# USB_MUX.net
KiCad netlist of a schematic drawn in Altium Designer
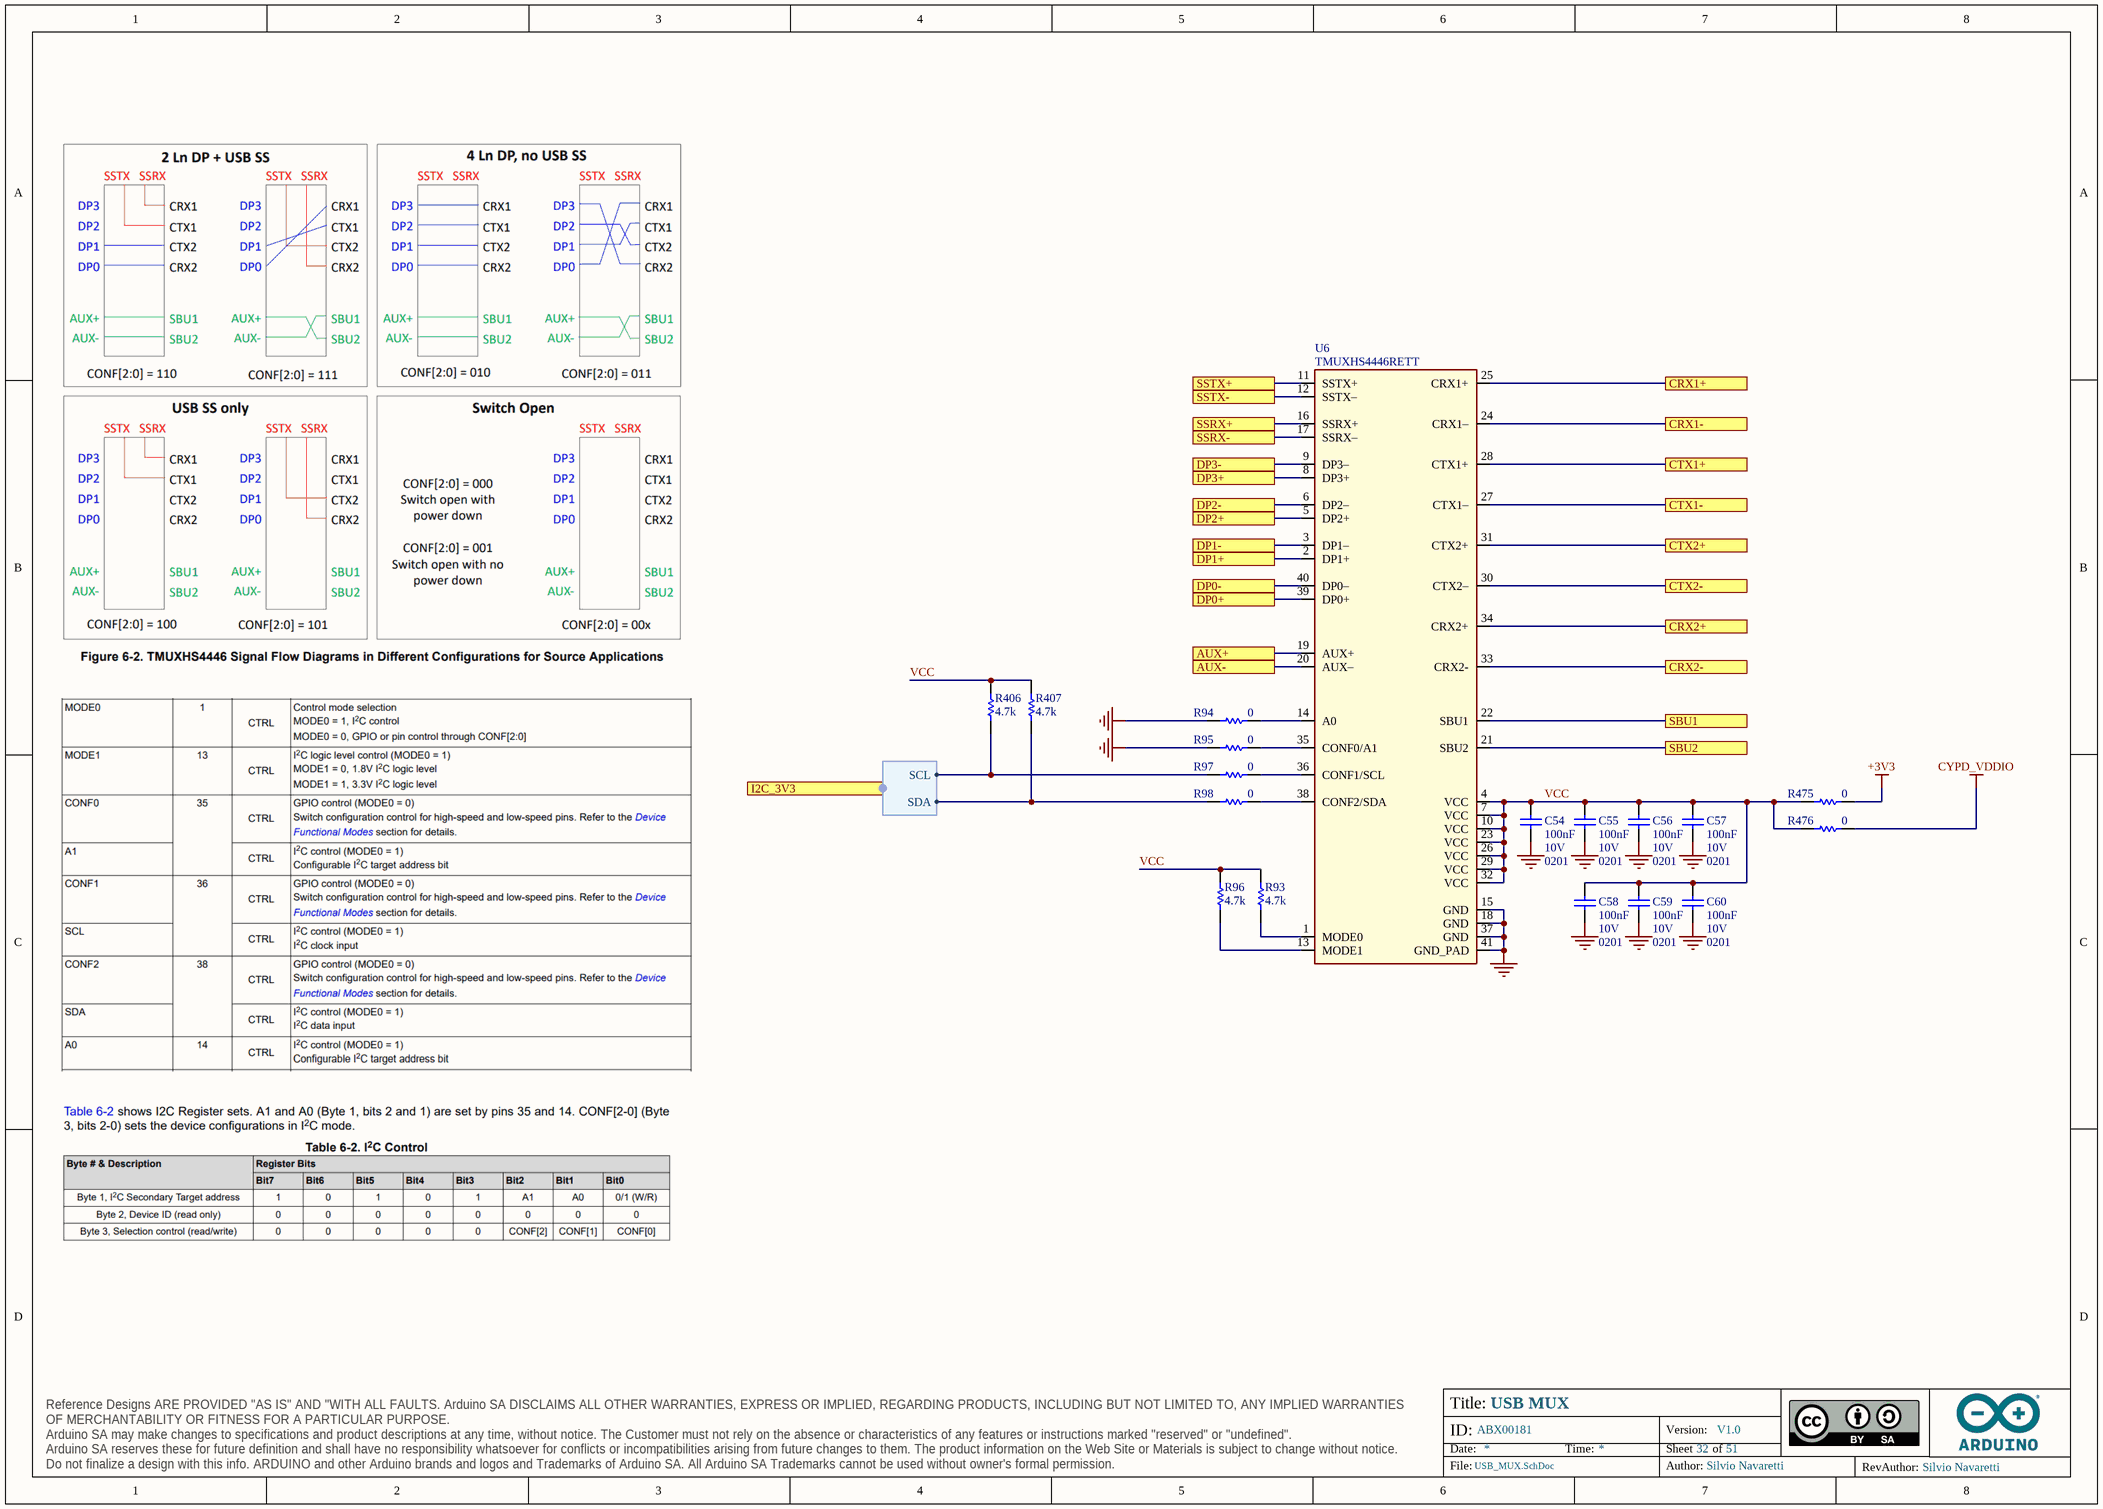
[diagram p0: USB_MUX.SchDoc]

(export (version "E")
  (design (tool "Eeschema 10.0.6"))
  (components
    (comp (ref "C54")
      (value "100nF")
      (footprint "CAP-0201")
      (description "CAP CHIP 0201 100nF 10% 10V X5R")
      (fields
        (field (name "PART NUMBER") "CL03A104KP3NNNC")
        (field (name "MANUFACTURER") "Samsung Electro-Mechanics")
        (field (name "VOLTAGE") "10V")
        (field (name "CASE CODE (IMPERIAL)") "0201")
      )
      (libsource (lib "Clean") (part "CAP"))
    )
    (comp (ref "C55")
      (value "100nF")
      (footprint "CAP-0201")
      (description "CAP CHIP 0201 100nF 10% 10V X5R")
      (fields
        (field (name "PART NUMBER") "CL03A104KP3NNNC")
        (field (name "MANUFACTURER") "Samsung Electro-Mechanics")
        (field (name "VOLTAGE") "10V")
        (field (name "CASE CODE (IMPERIAL)") "0201")
      )
      (libsource (lib "Clean") (part "CAP"))
    )
    (comp (ref "C56")
      (value "100nF")
      (footprint "CAP-0201")
      (description "CAP CHIP 0201 100nF 10% 10V X5R")
      (fields
        (field (name "PART NUMBER") "CL03A104KP3NNNC")
        (field (name "MANUFACTURER") "Samsung Electro-Mechanics")
        (field (name "VOLTAGE") "10V")
        (field (name "CASE CODE (IMPERIAL)") "0201")
      )
      (libsource (lib "Clean") (part "CAP"))
    )
    (comp (ref "C57")
      (value "100nF")
      (footprint "CAP-0201")
      (description "CAP CHIP 0201 100nF 10% 10V X5R")
      (fields
        (field (name "PART NUMBER") "CL03A104KP3NNNC")
        (field (name "MANUFACTURER") "Samsung Electro-Mechanics")
        (field (name "VOLTAGE") "10V")
        (field (name "CASE CODE (IMPERIAL)") "0201")
      )
      (libsource (lib "Clean") (part "CAP"))
    )
    (comp (ref "C58")
      (value "100nF")
      (footprint "CAP-0201")
      (description "CAP CHIP 0201 100nF 10% 10V X5R")
      (fields
        (field (name "PART NUMBER") "CL03A104KP3NNNC")
        (field (name "MANUFACTURER") "Samsung Electro-Mechanics")
        (field (name "VOLTAGE") "10V")
        (field (name "CASE CODE (IMPERIAL)") "0201")
      )
      (libsource (lib "Clean") (part "CAP"))
    )
    (comp (ref "C59")
      (value "100nF")
      (footprint "CAP-0201")
      (description "CAP CHIP 0201 100nF 10% 10V X5R")
      (fields
        (field (name "PART NUMBER") "CL03A104KP3NNNC")
        (field (name "MANUFACTURER") "Samsung Electro-Mechanics")
        (field (name "VOLTAGE") "10V")
        (field (name "CASE CODE (IMPERIAL)") "0201")
      )
      (libsource (lib "Clean") (part "CAP"))
    )
    (comp (ref "C60")
      (value "100nF")
      (footprint "CAP-0201")
      (description "CAP CHIP 0201 100nF 10% 10V X5R")
      (fields
        (field (name "PART NUMBER") "CL03A104KP3NNNC")
        (field (name "MANUFACTURER") "Samsung Electro-Mechanics")
        (field (name "VOLTAGE") "10V")
        (field (name "CASE CODE (IMPERIAL)") "0201")
      )
      (libsource (lib "Clean") (part "CAP"))
    )
    (comp (ref "R93")
      (value "4.7k")
      (footprint "RES-0201")
      (description "RES CHIP 0201 4k7 1% 1/20W")
      (fields (field (name "POWER") "50mW") (field (name "PART NUMBER") "RC0201FR-074K7L"))
      (libsource (lib "Clean") (part "RES"))
    )
    (comp (ref "R94")
      (value "0")
      (footprint "RES-0201")
      (description "RES CHIP 0201 0R")
      (fields (field (name "MANUFACTURER") "Vishay") (field (name "PART NUMBER") "CRCW02010000Z0ED"))
      (libsource (lib "Clean") (part "RES"))
    )
    (comp (ref "R95")
      (value "0")
      (footprint "RES-0201")
      (description "RES CHIP 0201 0R")
      (fields (field (name "MANUFACTURER") "Vishay") (field (name "PART NUMBER") "CRCW02010000Z0ED"))
      (libsource (lib "Clean") (part "RES"))
    )
    (comp (ref "R96")
      (value "4.7k")
      (footprint "RES-0201")
      (description "RES CHIP 0201 4k7 1% 1/20W")
      (fields (field (name "POWER") "50mW") (field (name "PART NUMBER") "RC0201FR-074K7L"))
      (libsource (lib "Clean") (part "RES"))
    )
    (comp (ref "R97")
      (value "0")
      (footprint "RES-0201")
      (description "RES CHIP 0201 0R")
      (fields (field (name "MANUFACTURER") "Vishay") (field (name "PART NUMBER") "CRCW02010000Z0ED"))
      (libsource (lib "Clean") (part "RES"))
    )
    (comp (ref "R98")
      (value "0")
      (footprint "RES-0201")
      (description "RES CHIP 0201 0R")
      (fields (field (name "MANUFACTURER") "Vishay") (field (name "PART NUMBER") "CRCW02010000Z0ED"))
      (libsource (lib "Clean") (part "RES"))
    )
    (comp (ref "R406")
      (value "4.7k")
      (footprint "RES-0201")
      (description "RES CHIP 0201 4k7 1% 1/20W")
      (fields (field (name "POWER") "50mW") (field (name "PART NUMBER") "RC0201FR-074K7L"))
      (libsource (lib "Clean") (part "RES"))
    )
    (comp (ref "R407")
      (value "4.7k")
      (footprint "RES-0201")
      (description "RES CHIP 0201 4k7 1% 1/20W")
      (fields (field (name "POWER") "50mW") (field (name "PART NUMBER") "RC0201FR-074K7L"))
      (libsource (lib "Clean") (part "RES"))
    )
    (comp (ref "R475")
      (value "0")
      (footprint "RES-0201")
      (description "RES CHIP 0201 0R")
      (fields (field (name "MANUFACTURER") "Vishay") (field (name "PART NUMBER") "CRCW02010000Z0ED"))
      (libsource (lib "Clean") (part "RES"))
    )
    (comp (ref "R476")
      (value "0")
      (footprint "RES-0201")
      (description "RES CHIP 0201 0R")
      (fields (field (name "MANUFACTURER") "Vishay") (field (name "PART NUMBER") "CRCW02010000Z0ED"))
      (libsource (lib "Clean") (part "RES"))
    )
    (comp (ref "U6")
      (value "TMUXHS4446RETT")
      (footprint "TI QWFN40 RET0040A Pitch 0.4mm 3x6mm")
      (description "IC MUX Alt Mode Crossbar USB-C 10Gbps, QFN40 3x6mm")
      (fields (field (name "MANUFACTURER") "Texas Instruments"))
      (libsource (lib "Clean") (part "TMUXHS4446RETT-Symbol-1"))
    )
  )
  (nets
    (net (code "2") (name "+3V3") (class "Default")
      (node (ref "R475") (pin "2") (pinfunction "2_2") (pintype "passive"))
    )
    (net (code "3") (name "/AUX+") (class "Default")
      (node (ref "U6") (pin "19") (pinfunction "AUX+_19") (pintype "passive"))
    )
    (net (code "4") (name "/AUX-") (class "Default")
      (node (ref "U6") (pin "20") (pinfunction "AUX–_20") (pintype "passive"))
    )
    (net (code "5") (name "/CRX1+") (class "Default")
      (node (ref "U6") (pin "25") (pinfunction "CRX1+_25") (pintype "passive"))
    )
    (net (code "6") (name "/CRX1-") (class "Default")
      (node (ref "U6") (pin "24") (pinfunction "CRX1–_24") (pintype "passive"))
    )
    (net (code "7") (name "/CRX2+") (class "Default")
      (node (ref "U6") (pin "34") (pinfunction "CRX2+_34") (pintype "passive"))
    )
    (net (code "8") (name "/CRX2-") (class "Default")
      (node (ref "U6") (pin "33") (pinfunction "CRX2-_33") (pintype "passive"))
    )
    (net (code "9") (name "/CTX1+") (class "Default")
      (node (ref "U6") (pin "28") (pinfunction "CTX1+_28") (pintype "passive"))
    )
    (net (code "10") (name "/CTX1-") (class "Default")
      (node (ref "U6") (pin "27") (pinfunction "CTX1–_27") (pintype "passive"))
    )
    (net (code "11") (name "/CTX2+") (class "Default")
      (node (ref "U6") (pin "31") (pinfunction "CTX2+_31") (pintype "passive"))
    )
    (net (code "12") (name "/CTX2-") (class "Default")
      (node (ref "U6") (pin "30") (pinfunction "CTX2–_30") (pintype "passive"))
    )
    (net (code "13") (name "/DP0+") (class "Default")
      (node (ref "U6") (pin "39") (pinfunction "DP0+_39") (pintype "passive"))
    )
    (net (code "14") (name "/DP0-") (class "Default")
      (node (ref "U6") (pin "40") (pinfunction "DP0–_40") (pintype "passive"))
    )
    (net (code "15") (name "/DP1+") (class "Default")
      (node (ref "U6") (pin "2") (pinfunction "DP1+_2") (pintype "passive"))
    )
    (net (code "16") (name "/DP1-") (class "Default")
      (node (ref "U6") (pin "3") (pinfunction "DP1–_3") (pintype "passive"))
    )
    (net (code "17") (name "/DP2+") (class "Default")
      (node (ref "U6") (pin "5") (pinfunction "DP2+_5") (pintype "passive"))
    )
    (net (code "18") (name "/DP2-") (class "Default")
      (node (ref "U6") (pin "6") (pinfunction "DP2–_6") (pintype "passive"))
    )
    (net (code "19") (name "/DP3+") (class "Default")
      (node (ref "U6") (pin "8") (pinfunction "DP3+_8") (pintype "passive"))
    )
    (net (code "20") (name "/DP3-") (class "Default")
      (node (ref "U6") (pin "9") (pinfunction "DP3–_9") (pintype "passive"))
    )
    (net (code "21") (name "/SBU1") (class "Default")
      (node (ref "U6") (pin "22") (pinfunction "SBU1_22") (pintype "passive"))
    )
    (net (code "22") (name "/SBU2") (class "Default")
      (node (ref "U6") (pin "21") (pinfunction "SBU2_21") (pintype "passive"))
    )
    (net (code "23") (name "/SSRX+") (class "Default")
      (node (ref "U6") (pin "16") (pinfunction "SSRX+_16") (pintype "passive"))
    )
    (net (code "24") (name "/SSRX-") (class "Default")
      (node (ref "U6") (pin "17") (pinfunction "SSRX–_17") (pintype "passive"))
    )
    (net (code "25") (name "/SSTX+") (class "Default")
      (node (ref "U6") (pin "11") (pinfunction "SSTX+_11") (pintype "passive"))
    )
    (net (code "26") (name "/SSTX-") (class "Default")
      (node (ref "U6") (pin "12") (pinfunction "SSTX–_12") (pintype "passive"))
    )
    (net (code "27") (name "/VCC") (class "Default")
      (node (ref "C54") (pin "2") (pinfunction "2_2") (pintype "passive"))
      (node (ref "C55") (pin "2") (pinfunction "2_2") (pintype "passive"))
      (node (ref "C56") (pin "2") (pinfunction "2_2") (pintype "passive"))
      (node (ref "C57") (pin "2") (pinfunction "2_2") (pintype "passive"))
      (node (ref "C58") (pin "2") (pinfunction "2_2") (pintype "passive"))
      (node (ref "C59") (pin "2") (pinfunction "2_2") (pintype "passive"))
      (node (ref "C60") (pin "2") (pinfunction "2_2") (pintype "passive"))
      (node (ref "R406") (pin "1") (pinfunction "1_1") (pintype "passive"))
      (node (ref "R407") (pin "1") (pinfunction "1_1") (pintype "passive"))
      (node (ref "R475") (pin "1") (pinfunction "1_1") (pintype "passive"))
      (node (ref "R476") (pin "1") (pinfunction "1_1") (pintype "passive"))
      (node (ref "R93") (pin "1") (pinfunction "1_1") (pintype "passive"))
      (node (ref "R96") (pin "1") (pinfunction "1_1") (pintype "passive"))
      (node (ref "U6") (pin "10") (pinfunction "VCC_10") (pintype "passive"))
      (node (ref "U6") (pin "23") (pinfunction "VCC_23") (pintype "passive"))
      (node (ref "U6") (pin "26") (pinfunction "VCC_26") (pintype "passive"))
      (node (ref "U6") (pin "29") (pinfunction "VCC_29") (pintype "passive"))
      (node (ref "U6") (pin "32") (pinfunction "VCC_32") (pintype "passive"))
      (node (ref "U6") (pin "4") (pinfunction "VCC_4") (pintype "passive"))
      (node (ref "U6") (pin "7") (pinfunction "VCC_7") (pintype "passive"))
    )
    (net (code "29") (name "CYPD_VDDIO") (class "Default")
      (node (ref "R476") (pin "2") (pinfunction "2_2") (pintype "passive"))
    )
    (net (code "30") (name "GND") (class "Default")
      (node (ref "C54") (pin "1") (pinfunction "1_1") (pintype "passive"))
      (node (ref "C55") (pin "1") (pinfunction "1_1") (pintype "passive"))
      (node (ref "C56") (pin "1") (pinfunction "1_1") (pintype "passive"))
      (node (ref "C57") (pin "1") (pinfunction "1_1") (pintype "passive"))
      (node (ref "C58") (pin "1") (pinfunction "1_1") (pintype "passive"))
      (node (ref "C59") (pin "1") (pinfunction "1_1") (pintype "passive"))
      (node (ref "C60") (pin "1") (pinfunction "1_1") (pintype "passive"))
      (node (ref "R94") (pin "1") (pinfunction "1_1") (pintype "passive"))
      (node (ref "R95") (pin "1") (pinfunction "1_1") (pintype "passive"))
      (node (ref "U6") (pin "15") (pinfunction "GND_15") (pintype "passive"))
      (node (ref "U6") (pin "18") (pinfunction "GND_18") (pintype "passive"))
      (node (ref "U6") (pin "37") (pinfunction "GND_37") (pintype "passive"))
      (node (ref "U6") (pin "41") (pinfunction "GND_PAD_41") (pintype "passive"))
    )
    (net (code "31") (name "Net-(R406-Pad2)") (class "Default")
      (node (ref "R406") (pin "2") (pinfunction "2_2") (pintype "passive"))
      (node (ref "R97") (pin "1") (pinfunction "1_1") (pintype "passive"))
    )
    (net (code "32") (name "Net-(R407-Pad2)") (class "Default")
      (node (ref "R407") (pin "2") (pinfunction "2_2") (pintype "passive"))
      (node (ref "R98") (pin "1") (pinfunction "1_1") (pintype "passive"))
    )
    (net (code "33") (name "Net-(U6-A0)") (class "Default")
      (node (ref "R94") (pin "2") (pinfunction "2_2") (pintype "passive"))
      (node (ref "U6") (pin "14") (pinfunction "A0_14") (pintype "passive"))
    )
    (net (code "34") (name "Net-(U6-CONF0{slash}A1)") (class "Default")
      (node (ref "R95") (pin "2") (pinfunction "2_2") (pintype "passive"))
      (node (ref "U6") (pin "35") (pinfunction "CONF0/A1_35") (pintype "passive"))
    )
    (net (code "35") (name "Net-(U6-CONF1{slash}SCL)") (class "Default")
      (node (ref "R97") (pin "2") (pinfunction "2_2") (pintype "passive"))
      (node (ref "U6") (pin "36") (pinfunction "CONF1/SCL_36") (pintype "passive"))
    )
    (net (code "36") (name "Net-(U6-CONF2{slash}SDA)") (class "Default")
      (node (ref "R98") (pin "2") (pinfunction "2_2") (pintype "passive"))
      (node (ref "U6") (pin "38") (pinfunction "CONF2/SDA_38") (pintype "passive"))
    )
    (net (code "37") (name "Net-(U6-MODE0)") (class "Default")
      (node (ref "R93") (pin "2") (pinfunction "2_2") (pintype "passive"))
      (node (ref "U6") (pin "1") (pinfunction "MODE0_1") (pintype "passive"))
    )
    (net (code "38") (name "Net-(U6-MODE1)") (class "Default")
      (node (ref "R96") (pin "2") (pinfunction "2_2") (pintype "passive"))
      (node (ref "U6") (pin "13") (pinfunction "MODE1_13") (pintype "passive"))
    )
  )
)
